# 1-Schematic_Macro_Pad.net
KiCad netlist of a schematic drawn in EasyEDA
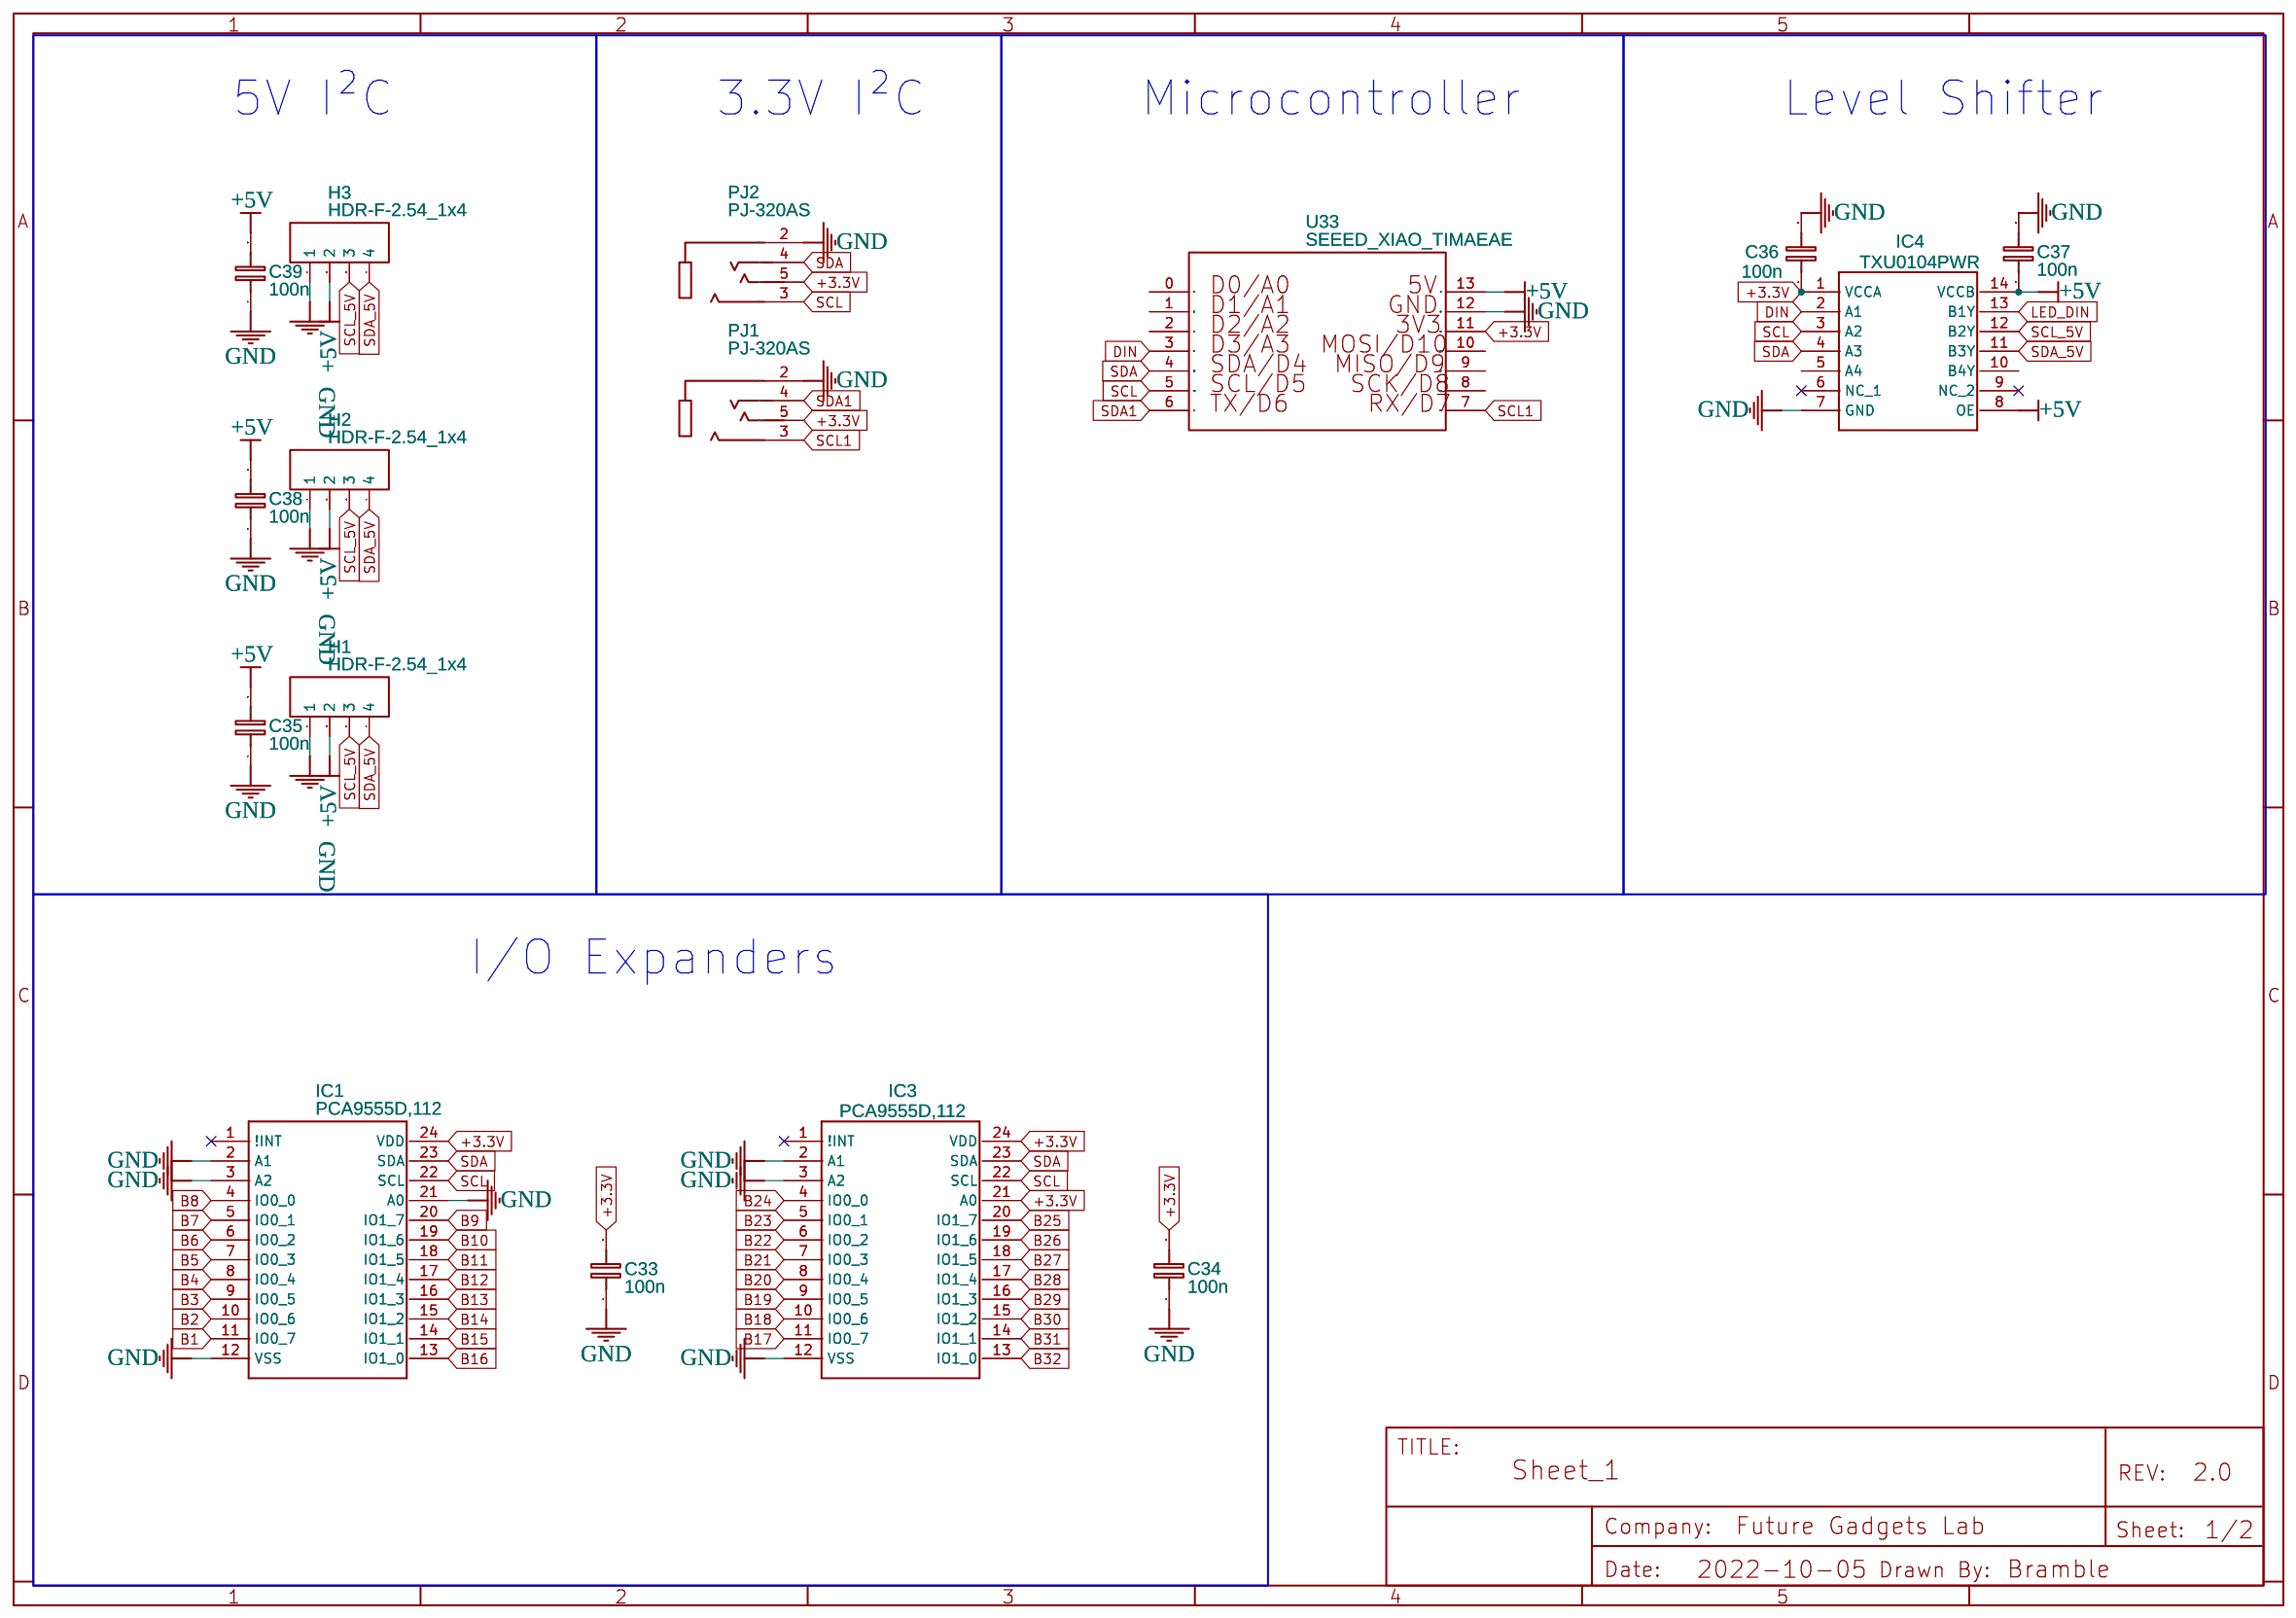
[diagram p0: Sheet_1]
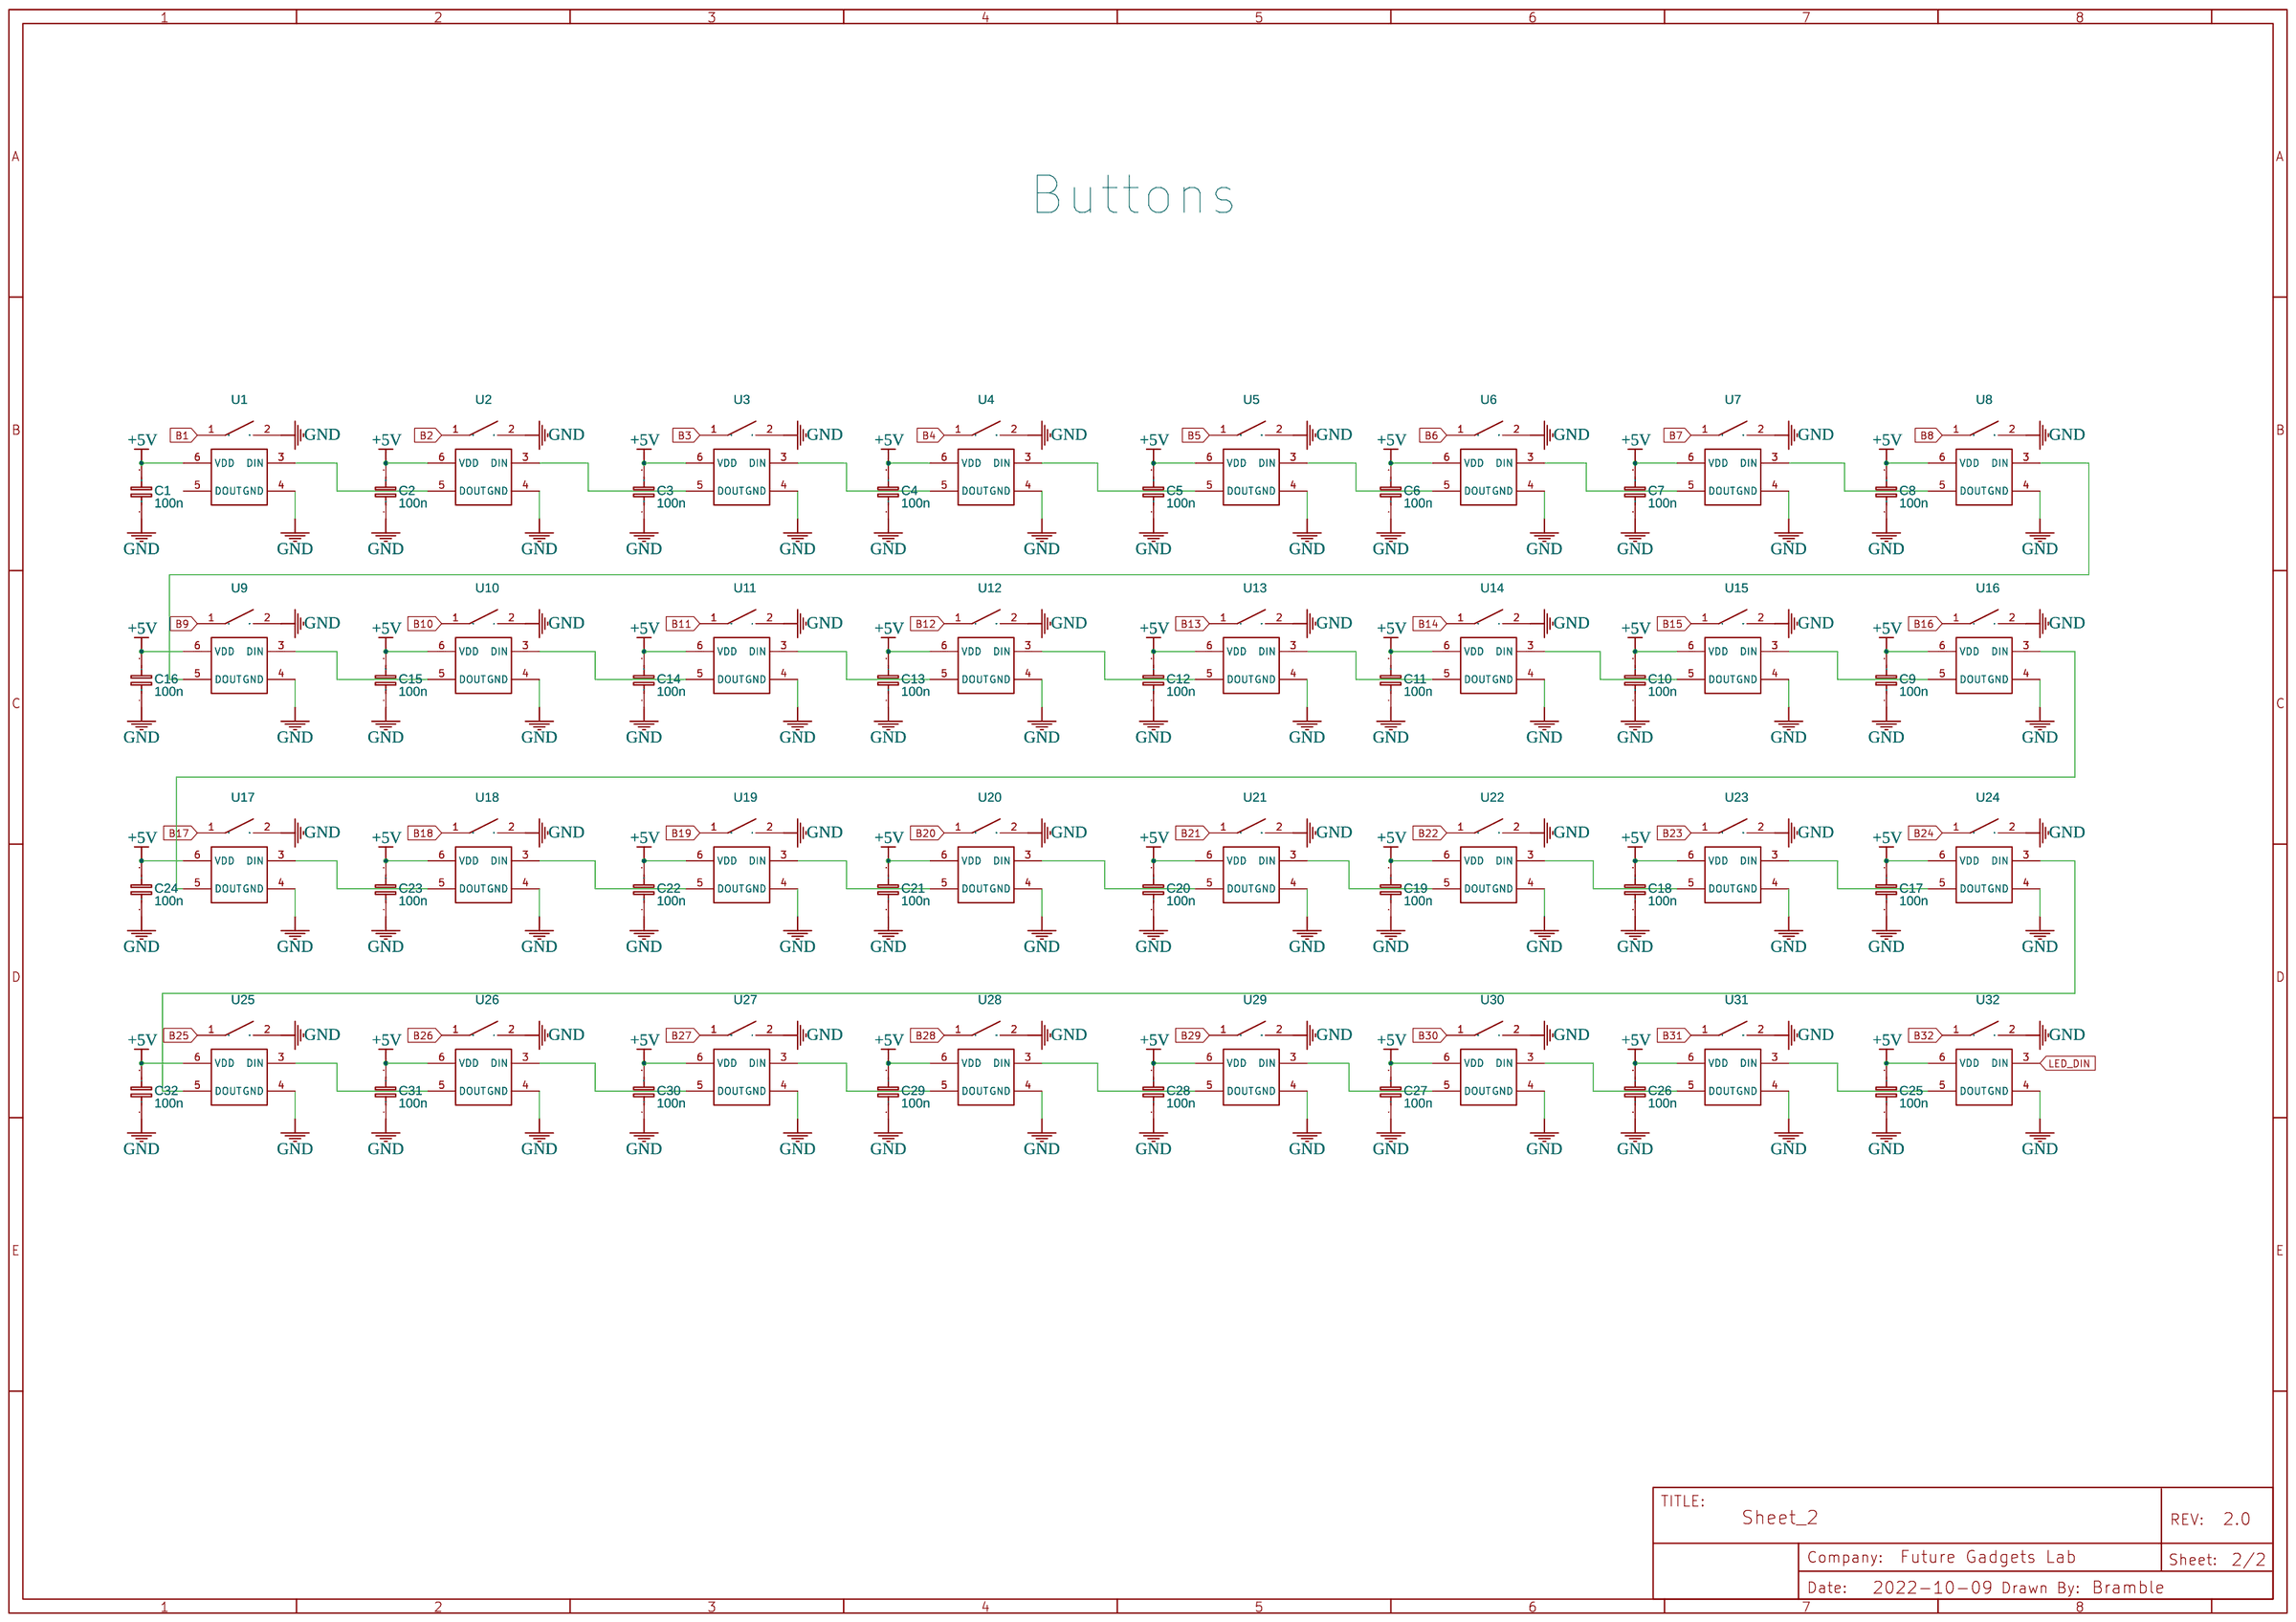
[diagram p1: Sheet_2]

(export (version "E")
  (design (tool "Eeschema 10.0.6"))
  (components
    (comp (ref "C33") (value "100n") (libsource (lib "") (part "C_0603_EU")))
    (comp (ref "C34") (value "100n") (libsource (lib "") (part "C_0603_EU_1")))
    (comp (ref "C35") (value "100n") (libsource (lib "") (part "C_0603_EU_1")))
    (comp (ref "C36") (value "100n") (libsource (lib "") (part "C_0603_EU_2")))
    (comp (ref "C37") (value "100n") (libsource (lib "") (part "C_0603_EU_2")))
    (comp (ref "C38") (value "100n") (libsource (lib "") (part "C_0603_EU_2")))
    (comp (ref "C39") (value "100n") (libsource (lib "") (part "C_0603_EU_2")))
    (comp (ref "H1")
      (value "HDR-F-2.54_1x4")
      (fields (field (name "BOM_Supplier Part") "C225501"))
      (libsource (lib "") (part "HDR-F-2.54_1x4"))
    )
    (comp (ref "H2")
      (value "HDR-F-2.54_1x4")
      (fields (field (name "BOM_Supplier Part") "C225501"))
      (libsource (lib "") (part "HDR-F-2.54_1x4"))
    )
    (comp (ref "H3")
      (value "HDR-F-2.54_1x4")
      (fields (field (name "BOM_Supplier Part") "C225501"))
      (libsource (lib "") (part "HDR-F-2.54_1x4"))
    )
    (comp (ref "IC1") (value "PCA9555D,112") (libsource (lib "") (part "PCA9555D,112")))
    (comp (ref "IC3") (value "PCA9555D,112") (libsource (lib "") (part "PCA9555D,112")))
    (comp (ref "IC4") (value "TXU0104PWR") (libsource (lib "") (part "TXU0104PWR")))
    (comp (ref "PJ1")
      (value "PJ-320AS")
      (fields (field (name "BOM_Supplier Part") "C2939182"))
      (libsource (lib "") (part "PJ-320AS"))
    )
    (comp (ref "PJ2")
      (value "PJ-320AS")
      (fields (field (name "BOM_Supplier Part") "C2939182"))
      (libsource (lib "") (part "PJ-320AS"))
    )
    (comp (ref "U33")
      (value "SEEED_XIAO_TIMAEAE")
      (fields (field (name "BOM_Manufacturer Part") "102010428"))
      (libsource (lib "") (part "SEEED_XIAO_TIMAEAE"))
    )
    (comp (ref "C1") (value "100n") (libsource (lib "") (part "C_0603_EU")))
    (comp (ref "C2") (value "100n") (libsource (lib "") (part "C_0603_EU_1")))
    (comp (ref "C3") (value "100n") (libsource (lib "") (part "C_0603_EU_1")))
    (comp (ref "C4") (value "100n") (libsource (lib "") (part "C_0603_EU")))
    (comp (ref "C5") (value "100n") (libsource (lib "") (part "C_0603_EU")))
    (comp (ref "C6") (value "100n") (libsource (lib "") (part "C_0603_EU")))
    (comp (ref "C7") (value "100n") (libsource (lib "") (part "C_0603_EU")))
    (comp (ref "C8") (value "100n") (libsource (lib "") (part "C_0603_EU")))
    (comp (ref "C9") (value "100n") (libsource (lib "") (part "C_0603_EU")))
    (comp (ref "C10") (value "100n") (libsource (lib "") (part "C_0603_EU")))
    (comp (ref "C11") (value "100n") (libsource (lib "") (part "C_0603_EU")))
    (comp (ref "C12") (value "100n") (libsource (lib "") (part "C_0603_EU")))
    (comp (ref "C13") (value "100n") (libsource (lib "") (part "C_0603_EU")))
    (comp (ref "C14") (value "100n") (libsource (lib "") (part "C_0603_EU_1")))
    (comp (ref "C15") (value "100n") (libsource (lib "") (part "C_0603_EU_1")))
    (comp (ref "C16") (value "100n") (libsource (lib "") (part "C_0603_EU")))
    (comp (ref "C17") (value "100n") (libsource (lib "") (part "C_0603_EU")))
    (comp (ref "C18") (value "100n") (libsource (lib "") (part "C_0603_EU")))
    (comp (ref "C19") (value "100n") (libsource (lib "") (part "C_0603_EU")))
    (comp (ref "C20") (value "100n") (libsource (lib "") (part "C_0603_EU")))
    (comp (ref "C21") (value "100n") (libsource (lib "") (part "C_0603_EU")))
    (comp (ref "C22") (value "100n") (libsource (lib "") (part "C_0603_EU_1")))
    (comp (ref "C23") (value "100n") (libsource (lib "") (part "C_0603_EU_1")))
    (comp (ref "C24") (value "100n") (libsource (lib "") (part "C_0603_EU")))
    (comp (ref "C25") (value "100n") (libsource (lib "") (part "C_0603_EU_3")))
    (comp (ref "C26") (value "100n") (libsource (lib "") (part "C_0603_EU_3")))
    (comp (ref "C27") (value "100n") (libsource (lib "") (part "C_0603_EU_3")))
    (comp (ref "C28") (value "100n") (libsource (lib "") (part "C_0603_EU_3")))
    (comp (ref "C29") (value "100n") (libsource (lib "") (part "C_0603_EU_3")))
    (comp (ref "C30") (value "100n") (libsource (lib "") (part "C_0603_EU_2")))
    (comp (ref "C31") (value "100n") (libsource (lib "") (part "C_0603_EU_2")))
    (comp (ref "C32") (value "100n") (libsource (lib "") (part "C_0603_EU_3")))
    (comp (ref "U1") (value "Hotswap MX/Choc 1*1") (libsource (lib "") (part "Hotswap MX/Choc 1*1")))
    (comp (ref "U2") (value "Hotswap MX/Choc 1*1") (libsource (lib "") (part "Hotswap MX/Choc 1*1")))
    (comp (ref "U3") (value "Hotswap MX/Choc 1*1") (libsource (lib "") (part "Hotswap MX/Choc 1*1")))
    (comp (ref "U4") (value "Hotswap MX/Choc 1*1") (libsource (lib "") (part "Hotswap MX/Choc 1*1")))
    (comp (ref "U5") (value "Hotswap MX/Choc 1*1") (libsource (lib "") (part "Hotswap MX/Choc 1*1")))
    (comp (ref "U6") (value "Hotswap MX/Choc 1*1") (libsource (lib "") (part "Hotswap MX/Choc 1*1")))
    (comp (ref "U7") (value "Hotswap MX/Choc 1*1") (libsource (lib "") (part "Hotswap MX/Choc 1*1")))
    (comp (ref "U8") (value "Hotswap MX/Choc 1*1") (libsource (lib "") (part "Hotswap MX/Choc 1*1")))
    (comp (ref "U9") (value "Hotswap MX/Choc 1*1") (libsource (lib "") (part "Hotswap MX/Choc 1*1")))
    (comp (ref "U10") (value "Hotswap MX/Choc 1*1") (libsource (lib "") (part "Hotswap MX/Choc 1*1")))
    (comp (ref "U11") (value "Hotswap MX/Choc 1*1") (libsource (lib "") (part "Hotswap MX/Choc 1*1")))
    (comp (ref "U12") (value "Hotswap MX/Choc 1*1") (libsource (lib "") (part "Hotswap MX/Choc 1*1")))
    (comp (ref "U13") (value "Hotswap MX/Choc 1*1") (libsource (lib "") (part "Hotswap MX/Choc 1*1")))
    (comp (ref "U14") (value "Hotswap MX/Choc 1*1") (libsource (lib "") (part "Hotswap MX/Choc 1*1")))
    (comp (ref "U15") (value "Hotswap MX/Choc 1*1") (libsource (lib "") (part "Hotswap MX/Choc 1*1")))
    (comp (ref "U16") (value "Hotswap MX/Choc 1*1") (libsource (lib "") (part "Hotswap MX/Choc 1*1")))
    (comp (ref "U17") (value "Hotswap MX/Choc 1*1") (libsource (lib "") (part "Hotswap MX/Choc 1*1")))
    (comp (ref "U18") (value "Hotswap MX/Choc 1*1") (libsource (lib "") (part "Hotswap MX/Choc 1*1")))
    (comp (ref "U19") (value "Hotswap MX/Choc 1*1") (libsource (lib "") (part "Hotswap MX/Choc 1*1")))
    (comp (ref "U20") (value "Hotswap MX/Choc 1*1") (libsource (lib "") (part "Hotswap MX/Choc 1*1")))
    (comp (ref "U21") (value "Hotswap MX/Choc 1*1") (libsource (lib "") (part "Hotswap MX/Choc 1*1")))
    (comp (ref "U22") (value "Hotswap MX/Choc 1*1") (libsource (lib "") (part "Hotswap MX/Choc 1*1")))
    (comp (ref "U23") (value "Hotswap MX/Choc 1*1") (libsource (lib "") (part "Hotswap MX/Choc 1*1")))
    (comp (ref "U24") (value "Hotswap MX/Choc 1*1") (libsource (lib "") (part "Hotswap MX/Choc 1*1")))
    (comp (ref "U25") (value "Hotswap MX/Choc 1*1") (libsource (lib "") (part "Hotswap MX/Choc 1*1")))
    (comp (ref "U26") (value "Hotswap MX/Choc 1*1") (libsource (lib "") (part "Hotswap MX/Choc 1*1")))
    (comp (ref "U27") (value "Hotswap MX/Choc 1*1") (libsource (lib "") (part "Hotswap MX/Choc 1*1")))
    (comp (ref "U28") (value "Hotswap MX/Choc 1*1") (libsource (lib "") (part "Hotswap MX/Choc 1*1")))
    (comp (ref "U29") (value "Hotswap MX/Choc 1*1") (libsource (lib "") (part "Hotswap MX/Choc 1*1")))
    (comp (ref "U30") (value "Hotswap MX/Choc 1*1") (libsource (lib "") (part "Hotswap MX/Choc 1*1")))
    (comp (ref "U31") (value "Hotswap MX/Choc 1*1") (libsource (lib "") (part "Hotswap MX/Choc 1*1")))
    (comp (ref "U32") (value "Hotswap MX/Choc 1*1") (libsource (lib "") (part "Hotswap MX/Choc 1*1")))
  )
  (nets
    (net (code "1") (name "+3.3V") (class "Default")
      (node (ref "C33") (pin "2") (pinfunction "2_2") (pintype "unspecified"))
      (node (ref "C34") (pin "2") (pinfunction "2_2") (pintype "unspecified"))
      (node (ref "C36") (pin "1") (pinfunction "1_1") (pintype "unspecified"))
      (node (ref "IC1") (pin "24") (pinfunction "VDD_24") (pintype "bidirectional"))
      (node (ref "IC3") (pin "21") (pinfunction "A0_21") (pintype "bidirectional"))
      (node (ref "IC3") (pin "24") (pinfunction "VDD_24") (pintype "bidirectional"))
      (node (ref "IC4") (pin "1") (pinfunction "VCCA_1") (pintype "bidirectional"))
      (node (ref "PJ1") (pin "5") (pinfunction "5_5") (pintype "unspecified"))
      (node (ref "PJ2") (pin "5") (pinfunction "5_5") (pintype "unspecified"))
      (node (ref "U33") (pin "11") (pinfunction "3V3_11") (pintype "unspecified"))
    )
    (net (code "2") (name "+5V") (class "Default")
      (node (ref "C1") (pin "2") (pinfunction "2_2") (pintype "unspecified"))
      (node (ref "C10") (pin "2") (pinfunction "2_2") (pintype "unspecified"))
      (node (ref "C11") (pin "2") (pinfunction "2_2") (pintype "unspecified"))
      (node (ref "C12") (pin "2") (pinfunction "2_2") (pintype "unspecified"))
      (node (ref "C13") (pin "2") (pinfunction "2_2") (pintype "unspecified"))
      (node (ref "C14") (pin "2") (pinfunction "2_2") (pintype "unspecified"))
      (node (ref "C15") (pin "2") (pinfunction "2_2") (pintype "unspecified"))
      (node (ref "C16") (pin "2") (pinfunction "2_2") (pintype "unspecified"))
      (node (ref "C17") (pin "2") (pinfunction "2_2") (pintype "unspecified"))
      (node (ref "C18") (pin "2") (pinfunction "2_2") (pintype "unspecified"))
      (node (ref "C19") (pin "2") (pinfunction "2_2") (pintype "unspecified"))
      (node (ref "C2") (pin "2") (pinfunction "2_2") (pintype "unspecified"))
      (node (ref "C20") (pin "2") (pinfunction "2_2") (pintype "unspecified"))
      (node (ref "C21") (pin "2") (pinfunction "2_2") (pintype "unspecified"))
      (node (ref "C22") (pin "2") (pinfunction "2_2") (pintype "unspecified"))
      (node (ref "C23") (pin "2") (pinfunction "2_2") (pintype "unspecified"))
      (node (ref "C24") (pin "2") (pinfunction "2_2") (pintype "unspecified"))
      (node (ref "C25") (pin "2") (pinfunction "2_2") (pintype "unspecified"))
      (node (ref "C26") (pin "2") (pinfunction "2_2") (pintype "unspecified"))
      (node (ref "C27") (pin "2") (pinfunction "2_2") (pintype "unspecified"))
      (node (ref "C28") (pin "2") (pinfunction "2_2") (pintype "unspecified"))
      (node (ref "C29") (pin "2") (pinfunction "2_2") (pintype "unspecified"))
      (node (ref "C3") (pin "2") (pinfunction "2_2") (pintype "unspecified"))
      (node (ref "C30") (pin "2") (pinfunction "2_2") (pintype "unspecified"))
      (node (ref "C31") (pin "2") (pinfunction "2_2") (pintype "unspecified"))
      (node (ref "C32") (pin "2") (pinfunction "2_2") (pintype "unspecified"))
      (node (ref "C35") (pin "2") (pinfunction "2_2") (pintype "unspecified"))
      (node (ref "C37") (pin "1") (pinfunction "1_1") (pintype "unspecified"))
      (node (ref "C38") (pin "2") (pinfunction "2_2") (pintype "unspecified"))
      (node (ref "C39") (pin "2") (pinfunction "2_2") (pintype "unspecified"))
      (node (ref "C4") (pin "2") (pinfunction "2_2") (pintype "unspecified"))
      (node (ref "C5") (pin "2") (pinfunction "2_2") (pintype "unspecified"))
      (node (ref "C6") (pin "2") (pinfunction "2_2") (pintype "unspecified"))
      (node (ref "C7") (pin "2") (pinfunction "2_2") (pintype "unspecified"))
      (node (ref "C8") (pin "2") (pinfunction "2_2") (pintype "unspecified"))
      (node (ref "C9") (pin "2") (pinfunction "2_2") (pintype "unspecified"))
      (node (ref "H1") (pin "2") (pinfunction "2_2") (pintype "unspecified"))
      (node (ref "H2") (pin "2") (pinfunction "2_2") (pintype "unspecified"))
      (node (ref "H3") (pin "2") (pinfunction "2_2") (pintype "unspecified"))
      (node (ref "IC4") (pin "14") (pinfunction "VCCB_14") (pintype "bidirectional"))
      (node (ref "IC4") (pin "8") (pinfunction "OE_8") (pintype "bidirectional"))
      (node (ref "U1") (pin "6") (pinfunction "VDD_6") (pintype "unspecified"))
      (node (ref "U10") (pin "6") (pinfunction "VDD_6") (pintype "unspecified"))
      (node (ref "U11") (pin "6") (pinfunction "VDD_6") (pintype "unspecified"))
      (node (ref "U12") (pin "6") (pinfunction "VDD_6") (pintype "unspecified"))
      (node (ref "U13") (pin "6") (pinfunction "VDD_6") (pintype "unspecified"))
      (node (ref "U14") (pin "6") (pinfunction "VDD_6") (pintype "unspecified"))
      (node (ref "U15") (pin "6") (pinfunction "VDD_6") (pintype "unspecified"))
      (node (ref "U16") (pin "6") (pinfunction "VDD_6") (pintype "unspecified"))
      (node (ref "U17") (pin "6") (pinfunction "VDD_6") (pintype "unspecified"))
      (node (ref "U18") (pin "6") (pinfunction "VDD_6") (pintype "unspecified"))
      (node (ref "U19") (pin "6") (pinfunction "VDD_6") (pintype "unspecified"))
      (node (ref "U2") (pin "6") (pinfunction "VDD_6") (pintype "unspecified"))
      (node (ref "U20") (pin "6") (pinfunction "VDD_6") (pintype "unspecified"))
      (node (ref "U21") (pin "6") (pinfunction "VDD_6") (pintype "unspecified"))
      (node (ref "U22") (pin "6") (pinfunction "VDD_6") (pintype "unspecified"))
      (node (ref "U23") (pin "6") (pinfunction "VDD_6") (pintype "unspecified"))
      (node (ref "U24") (pin "6") (pinfunction "VDD_6") (pintype "unspecified"))
      (node (ref "U25") (pin "6") (pinfunction "VDD_6") (pintype "unspecified"))
      (node (ref "U26") (pin "6") (pinfunction "VDD_6") (pintype "unspecified"))
      (node (ref "U27") (pin "6") (pinfunction "VDD_6") (pintype "unspecified"))
      (node (ref "U28") (pin "6") (pinfunction "VDD_6") (pintype "unspecified"))
      (node (ref "U29") (pin "6") (pinfunction "VDD_6") (pintype "unspecified"))
      (node (ref "U3") (pin "6") (pinfunction "VDD_6") (pintype "unspecified"))
      (node (ref "U30") (pin "6") (pinfunction "VDD_6") (pintype "unspecified"))
      (node (ref "U31") (pin "6") (pinfunction "VDD_6") (pintype "unspecified"))
      (node (ref "U32") (pin "6") (pinfunction "VDD_6") (pintype "unspecified"))
      (node (ref "U33") (pin "13") (pinfunction "SV_13") (pintype "unspecified"))
      (node (ref "U4") (pin "6") (pinfunction "VDD_6") (pintype "unspecified"))
      (node (ref "U5") (pin "6") (pinfunction "VDD_6") (pintype "unspecified"))
      (node (ref "U6") (pin "6") (pinfunction "VDD_6") (pintype "unspecified"))
      (node (ref "U7") (pin "6") (pinfunction "VDD_6") (pintype "unspecified"))
      (node (ref "U8") (pin "6") (pinfunction "VDD_6") (pintype "unspecified"))
      (node (ref "U9") (pin "6") (pinfunction "VDD_6") (pintype "unspecified"))
    )
    (net (code "3") (name "B1") (class "Default")
      (node (ref "IC1") (pin "11") (pinfunction "IO0_7_11") (pintype "bidirectional"))
      (node (ref "U1") (pin "1") (pinfunction "SW1_1") (pintype "unspecified"))
    )
    (net (code "4") (name "B2") (class "Default")
      (node (ref "IC1") (pin "10") (pinfunction "IO0_6_10") (pintype "bidirectional"))
      (node (ref "U2") (pin "1") (pinfunction "SW1_1") (pintype "unspecified"))
    )
    (net (code "5") (name "B3") (class "Default")
      (node (ref "IC1") (pin "9") (pinfunction "IO0_5_9") (pintype "bidirectional"))
      (node (ref "U3") (pin "1") (pinfunction "SW1_1") (pintype "unspecified"))
    )
    (net (code "6") (name "B4") (class "Default")
      (node (ref "IC1") (pin "8") (pinfunction "IO0_4_8") (pintype "bidirectional"))
      (node (ref "U4") (pin "1") (pinfunction "SW1_1") (pintype "unspecified"))
    )
    (net (code "7") (name "B5") (class "Default")
      (node (ref "IC1") (pin "7") (pinfunction "IO0_3_7") (pintype "bidirectional"))
      (node (ref "U5") (pin "1") (pinfunction "SW1_1") (pintype "unspecified"))
    )
    (net (code "8") (name "B6") (class "Default")
      (node (ref "IC1") (pin "6") (pinfunction "IO0_2_6") (pintype "bidirectional"))
      (node (ref "U6") (pin "1") (pinfunction "SW1_1") (pintype "unspecified"))
    )
    (net (code "9") (name "B7") (class "Default")
      (node (ref "IC1") (pin "5") (pinfunction "IO0_1_5") (pintype "bidirectional"))
      (node (ref "U7") (pin "1") (pinfunction "SW1_1") (pintype "unspecified"))
    )
    (net (code "10") (name "B8") (class "Default")
      (node (ref "IC1") (pin "4") (pinfunction "IO0_0_4") (pintype "bidirectional"))
      (node (ref "U8") (pin "1") (pinfunction "SW1_1") (pintype "unspecified"))
    )
    (net (code "11") (name "B9") (class "Default")
      (node (ref "IC1") (pin "20") (pinfunction "IO1_7_20") (pintype "bidirectional"))
      (node (ref "U9") (pin "1") (pinfunction "SW1_1") (pintype "unspecified"))
    )
    (net (code "12") (name "B10") (class "Default")
      (node (ref "IC1") (pin "19") (pinfunction "IO1_6_19") (pintype "bidirectional"))
      (node (ref "U10") (pin "1") (pinfunction "SW1_1") (pintype "unspecified"))
    )
    (net (code "13") (name "B11") (class "Default")
      (node (ref "IC1") (pin "18") (pinfunction "IO1_5_18") (pintype "bidirectional"))
      (node (ref "U11") (pin "1") (pinfunction "SW1_1") (pintype "unspecified"))
    )
    (net (code "14") (name "B12") (class "Default")
      (node (ref "IC1") (pin "17") (pinfunction "IO1_4_17") (pintype "bidirectional"))
      (node (ref "U12") (pin "1") (pinfunction "SW1_1") (pintype "unspecified"))
    )
    (net (code "15") (name "B13") (class "Default")
      (node (ref "IC1") (pin "16") (pinfunction "IO1_3_16") (pintype "bidirectional"))
      (node (ref "U13") (pin "1") (pinfunction "SW1_1") (pintype "unspecified"))
    )
    (net (code "16") (name "B14") (class "Default")
      (node (ref "IC1") (pin "15") (pinfunction "IO1_2_15") (pintype "bidirectional"))
      (node (ref "U14") (pin "1") (pinfunction "SW1_1") (pintype "unspecified"))
    )
    (net (code "17") (name "B15") (class "Default")
      (node (ref "IC1") (pin "14") (pinfunction "IO1_1_14") (pintype "bidirectional"))
      (node (ref "U15") (pin "1") (pinfunction "SW1_1") (pintype "unspecified"))
    )
    (net (code "18") (name "B16") (class "Default")
      (node (ref "IC1") (pin "13") (pinfunction "IO1_0_13") (pintype "bidirectional"))
      (node (ref "U16") (pin "1") (pinfunction "SW1_1") (pintype "unspecified"))
    )
    (net (code "19") (name "B17") (class "Default")
      (node (ref "IC3") (pin "11") (pinfunction "IO0_7_11") (pintype "bidirectional"))
      (node (ref "U17") (pin "1") (pinfunction "SW1_1") (pintype "unspecified"))
    )
    (net (code "20") (name "B18") (class "Default")
      (node (ref "IC3") (pin "10") (pinfunction "IO0_6_10") (pintype "bidirectional"))
      (node (ref "U18") (pin "1") (pinfunction "SW1_1") (pintype "unspecified"))
    )
    (net (code "21") (name "B19") (class "Default")
      (node (ref "IC3") (pin "9") (pinfunction "IO0_5_9") (pintype "bidirectional"))
      (node (ref "U19") (pin "1") (pinfunction "SW1_1") (pintype "unspecified"))
    )
    (net (code "22") (name "B20") (class "Default")
      (node (ref "IC3") (pin "8") (pinfunction "IO0_4_8") (pintype "bidirectional"))
      (node (ref "U20") (pin "1") (pinfunction "SW1_1") (pintype "unspecified"))
    )
    (net (code "23") (name "B21") (class "Default")
      (node (ref "IC3") (pin "7") (pinfunction "IO0_3_7") (pintype "bidirectional"))
      (node (ref "U21") (pin "1") (pinfunction "SW1_1") (pintype "unspecified"))
    )
    (net (code "24") (name "B22") (class "Default")
      (node (ref "IC3") (pin "6") (pinfunction "IO0_2_6") (pintype "bidirectional"))
      (node (ref "U22") (pin "1") (pinfunction "SW1_1") (pintype "unspecified"))
    )
    (net (code "25") (name "B23") (class "Default")
      (node (ref "IC3") (pin "5") (pinfunction "IO0_1_5") (pintype "bidirectional"))
      (node (ref "U23") (pin "1") (pinfunction "SW1_1") (pintype "unspecified"))
    )
    (net (code "26") (name "B24") (class "Default")
      (node (ref "IC3") (pin "4") (pinfunction "IO0_0_4") (pintype "bidirectional"))
      (node (ref "U24") (pin "1") (pinfunction "SW1_1") (pintype "unspecified"))
    )
    (net (code "27") (name "B25") (class "Default")
      (node (ref "IC3") (pin "20") (pinfunction "IO1_7_20") (pintype "bidirectional"))
      (node (ref "U25") (pin "1") (pinfunction "SW1_1") (pintype "unspecified"))
    )
    (net (code "28") (name "B26") (class "Default")
      (node (ref "IC3") (pin "19") (pinfunction "IO1_6_19") (pintype "bidirectional"))
      (node (ref "U26") (pin "1") (pinfunction "SW1_1") (pintype "unspecified"))
    )
    (net (code "29") (name "B27") (class "Default")
      (node (ref "IC3") (pin "18") (pinfunction "IO1_5_18") (pintype "bidirectional"))
      (node (ref "U27") (pin "1") (pinfunction "SW1_1") (pintype "unspecified"))
    )
    (net (code "30") (name "B28") (class "Default")
      (node (ref "IC3") (pin "17") (pinfunction "IO1_4_17") (pintype "bidirectional"))
      (node (ref "U28") (pin "1") (pinfunction "SW1_1") (pintype "unspecified"))
    )
    (net (code "31") (name "B29") (class "Default")
      (node (ref "IC3") (pin "16") (pinfunction "IO1_3_16") (pintype "bidirectional"))
      (node (ref "U29") (pin "1") (pinfunction "SW1_1") (pintype "unspecified"))
    )
    (net (code "32") (name "B30") (class "Default")
      (node (ref "IC3") (pin "15") (pinfunction "IO1_2_15") (pintype "bidirectional"))
      (node (ref "U30") (pin "1") (pinfunction "SW1_1") (pintype "unspecified"))
    )
    (net (code "33") (name "B31") (class "Default")
      (node (ref "IC3") (pin "14") (pinfunction "IO1_1_14") (pintype "bidirectional"))
      (node (ref "U31") (pin "1") (pinfunction "SW1_1") (pintype "unspecified"))
    )
    (net (code "34") (name "B32") (class "Default")
      (node (ref "IC3") (pin "13") (pinfunction "IO1_0_13") (pintype "bidirectional"))
      (node (ref "U32") (pin "1") (pinfunction "SW1_1") (pintype "unspecified"))
    )
    (net (code "35") (name "DIN") (class "Default")
      (node (ref "IC4") (pin "2") (pinfunction "A1_2") (pintype "bidirectional"))
      (node (ref "U33") (pin "3") (pinfunction "D3/A3_3") (pintype "unspecified"))
    )
    (net (code "36") (name "GND") (class "Default")
      (node (ref "C1") (pin "1") (pinfunction "1_1") (pintype "unspecified"))
      (node (ref "C10") (pin "1") (pinfunction "1_1") (pintype "unspecified"))
      (node (ref "C11") (pin "1") (pinfunction "1_1") (pintype "unspecified"))
      (node (ref "C12") (pin "1") (pinfunction "1_1") (pintype "unspecified"))
      (node (ref "C13") (pin "1") (pinfunction "1_1") (pintype "unspecified"))
      (node (ref "C14") (pin "1") (pinfunction "1_1") (pintype "unspecified"))
      (node (ref "C15") (pin "1") (pinfunction "1_1") (pintype "unspecified"))
      (node (ref "C16") (pin "1") (pinfunction "1_1") (pintype "unspecified"))
      (node (ref "C17") (pin "1") (pinfunction "1_1") (pintype "unspecified"))
      (node (ref "C18") (pin "1") (pinfunction "1_1") (pintype "unspecified"))
      (node (ref "C19") (pin "1") (pinfunction "1_1") (pintype "unspecified"))
      (node (ref "C2") (pin "1") (pinfunction "1_1") (pintype "unspecified"))
      (node (ref "C20") (pin "1") (pinfunction "1_1") (pintype "unspecified"))
      (node (ref "C21") (pin "1") (pinfunction "1_1") (pintype "unspecified"))
      (node (ref "C22") (pin "1") (pinfunction "1_1") (pintype "unspecified"))
      (node (ref "C23") (pin "1") (pinfunction "1_1") (pintype "unspecified"))
      (node (ref "C24") (pin "1") (pinfunction "1_1") (pintype "unspecified"))
      (node (ref "C25") (pin "1") (pinfunction "1_1") (pintype "unspecified"))
      (node (ref "C26") (pin "1") (pinfunction "1_1") (pintype "unspecified"))
      (node (ref "C27") (pin "1") (pinfunction "1_1") (pintype "unspecified"))
      (node (ref "C28") (pin "1") (pinfunction "1_1") (pintype "unspecified"))
      (node (ref "C29") (pin "1") (pinfunction "1_1") (pintype "unspecified"))
      (node (ref "C3") (pin "1") (pinfunction "1_1") (pintype "unspecified"))
      (node (ref "C30") (pin "1") (pinfunction "1_1") (pintype "unspecified"))
      (node (ref "C31") (pin "1") (pinfunction "1_1") (pintype "unspecified"))
      (node (ref "C32") (pin "1") (pinfunction "1_1") (pintype "unspecified"))
      (node (ref "C33") (pin "1") (pinfunction "1_1") (pintype "unspecified"))
      (node (ref "C34") (pin "1") (pinfunction "1_1") (pintype "unspecified"))
      (node (ref "C35") (pin "1") (pinfunction "1_1") (pintype "unspecified"))
      (node (ref "C36") (pin "2") (pinfunction "2_2") (pintype "unspecified"))
      (node (ref "C37") (pin "2") (pinfunction "2_2") (pintype "unspecified"))
      (node (ref "C38") (pin "1") (pinfunction "1_1") (pintype "unspecified"))
      (node (ref "C39") (pin "1") (pinfunction "1_1") (pintype "unspecified"))
      (node (ref "C4") (pin "1") (pinfunction "1_1") (pintype "unspecified"))
      (node (ref "C5") (pin "1") (pinfunction "1_1") (pintype "unspecified"))
      (node (ref "C6") (pin "1") (pinfunction "1_1") (pintype "unspecified"))
      (node (ref "C7") (pin "1") (pinfunction "1_1") (pintype "unspecified"))
      (node (ref "C8") (pin "1") (pinfunction "1_1") (pintype "unspecified"))
      (node (ref "C9") (pin "1") (pinfunction "1_1") (pintype "unspecified"))
      (node (ref "H1") (pin "1") (pinfunction "1_1") (pintype "unspecified"))
      (node (ref "H2") (pin "1") (pinfunction "1_1") (pintype "unspecified"))
      (node (ref "H3") (pin "1") (pinfunction "1_1") (pintype "unspecified"))
      (node (ref "IC1") (pin "12") (pinfunction "VSS_12") (pintype "bidirectional"))
      (node (ref "IC1") (pin "2") (pinfunction "A1_2") (pintype "bidirectional"))
      (node (ref "IC1") (pin "21") (pinfunction "A0_21") (pintype "bidirectional"))
      (node (ref "IC1") (pin "3") (pinfunction "A2_3") (pintype "bidirectional"))
      (node (ref "IC3") (pin "12") (pinfunction "VSS_12") (pintype "bidirectional"))
      (node (ref "IC3") (pin "2") (pinfunction "A1_2") (pintype "bidirectional"))
      (node (ref "IC3") (pin "3") (pinfunction "A2_3") (pintype "bidirectional"))
      (node (ref "IC4") (pin "7") (pinfunction "GND_7") (pintype "bidirectional"))
      (node (ref "PJ1") (pin "2") (pinfunction "2_2") (pintype "unspecified"))
      (node (ref "PJ2") (pin "2") (pinfunction "2_2") (pintype "unspecified"))
      (node (ref "U1") (pin "2") (pinfunction "SW2_2") (pintype "unspecified"))
      (node (ref "U1") (pin "4") (pinfunction "GND_4") (pintype "unspecified"))
      (node (ref "U10") (pin "2") (pinfunction "SW2_2") (pintype "unspecified"))
      (node (ref "U10") (pin "4") (pinfunction "GND_4") (pintype "unspecified"))
      (node (ref "U11") (pin "2") (pinfunction "SW2_2") (pintype "unspecified"))
      (node (ref "U11") (pin "4") (pinfunction "GND_4") (pintype "unspecified"))
      (node (ref "U12") (pin "2") (pinfunction "SW2_2") (pintype "unspecified"))
      (node (ref "U12") (pin "4") (pinfunction "GND_4") (pintype "unspecified"))
      (node (ref "U13") (pin "2") (pinfunction "SW2_2") (pintype "unspecified"))
      (node (ref "U13") (pin "4") (pinfunction "GND_4") (pintype "unspecified"))
      (node (ref "U14") (pin "2") (pinfunction "SW2_2") (pintype "unspecified"))
      (node (ref "U14") (pin "4") (pinfunction "GND_4") (pintype "unspecified"))
      (node (ref "U15") (pin "2") (pinfunction "SW2_2") (pintype "unspecified"))
      (node (ref "U15") (pin "4") (pinfunction "GND_4") (pintype "unspecified"))
      (node (ref "U16") (pin "2") (pinfunction "SW2_2") (pintype "unspecified"))
      (node (ref "U16") (pin "4") (pinfunction "GND_4") (pintype "unspecified"))
      (node (ref "U17") (pin "2") (pinfunction "SW2_2") (pintype "unspecified"))
      (node (ref "U17") (pin "4") (pinfunction "GND_4") (pintype "unspecified"))
      (node (ref "U18") (pin "2") (pinfunction "SW2_2") (pintype "unspecified"))
      (node (ref "U18") (pin "4") (pinfunction "GND_4") (pintype "unspecified"))
      (node (ref "U19") (pin "2") (pinfunction "SW2_2") (pintype "unspecified"))
      (node (ref "U19") (pin "4") (pinfunction "GND_4") (pintype "unspecified"))
      (node (ref "U2") (pin "2") (pinfunction "SW2_2") (pintype "unspecified"))
      (node (ref "U2") (pin "4") (pinfunction "GND_4") (pintype "unspecified"))
      (node (ref "U20") (pin "2") (pinfunction "SW2_2") (pintype "unspecified"))
      (node (ref "U20") (pin "4") (pinfunction "GND_4") (pintype "unspecified"))
      (node (ref "U21") (pin "2") (pinfunction "SW2_2") (pintype "unspecified"))
      (node (ref "U21") (pin "4") (pinfunction "GND_4") (pintype "unspecified"))
      (node (ref "U22") (pin "2") (pinfunction "SW2_2") (pintype "unspecified"))
      (node (ref "U22") (pin "4") (pinfunction "GND_4") (pintype "unspecified"))
      (node (ref "U23") (pin "2") (pinfunction "SW2_2") (pintype "unspecified"))
      (node (ref "U23") (pin "4") (pinfunction "GND_4") (pintype "unspecified"))
      (node (ref "U24") (pin "2") (pinfunction "SW2_2") (pintype "unspecified"))
      (node (ref "U24") (pin "4") (pinfunction "GND_4") (pintype "unspecified"))
      (node (ref "U25") (pin "2") (pinfunction "SW2_2") (pintype "unspecified"))
      (node (ref "U25") (pin "4") (pinfunction "GND_4") (pintype "unspecified"))
      (node (ref "U26") (pin "2") (pinfunction "SW2_2") (pintype "unspecified"))
      (node (ref "U26") (pin "4") (pinfunction "GND_4") (pintype "unspecified"))
      (node (ref "U27") (pin "2") (pinfunction "SW2_2") (pintype "unspecified"))
      (node (ref "U27") (pin "4") (pinfunction "GND_4") (pintype "unspecified"))
      (node (ref "U28") (pin "2") (pinfunction "SW2_2") (pintype "unspecified"))
      (node (ref "U28") (pin "4") (pinfunction "GND_4") (pintype "unspecified"))
      (node (ref "U29") (pin "2") (pinfunction "SW2_2") (pintype "unspecified"))
      (node (ref "U29") (pin "4") (pinfunction "GND_4") (pintype "unspecified"))
      (node (ref "U3") (pin "2") (pinfunction "SW2_2") (pintype "unspecified"))
      (node (ref "U3") (pin "4") (pinfunction "GND_4") (pintype "unspecified"))
      (node (ref "U30") (pin "2") (pinfunction "SW2_2") (pintype "unspecified"))
      (node (ref "U30") (pin "4") (pinfunction "GND_4") (pintype "unspecified"))
      (node (ref "U31") (pin "2") (pinfunction "SW2_2") (pintype "unspecified"))
      (node (ref "U31") (pin "4") (pinfunction "GND_4") (pintype "unspecified"))
      (node (ref "U32") (pin "2") (pinfunction "SW2_2") (pintype "unspecified"))
      (node (ref "U32") (pin "4") (pinfunction "GND_4") (pintype "unspecified"))
      (node (ref "U33") (pin "12") (pinfunction "GND_12") (pintype "unspecified"))
      (node (ref "U4") (pin "2") (pinfunction "SW2_2") (pintype "unspecified"))
      (node (ref "U4") (pin "4") (pinfunction "GND_4") (pintype "unspecified"))
      (node (ref "U5") (pin "2") (pinfunction "SW2_2") (pintype "unspecified"))
      (node (ref "U5") (pin "4") (pinfunction "GND_4") (pintype "unspecified"))
      (node (ref "U6") (pin "2") (pinfunction "SW2_2") (pintype "unspecified"))
      (node (ref "U6") (pin "4") (pinfunction "GND_4") (pintype "unspecified"))
      (node (ref "U7") (pin "2") (pinfunction "SW2_2") (pintype "unspecified"))
      (node (ref "U7") (pin "4") (pinfunction "GND_4") (pintype "unspecified"))
      (node (ref "U8") (pin "2") (pinfunction "SW2_2") (pintype "unspecified"))
      (node (ref "U8") (pin "4") (pinfunction "GND_4") (pintype "unspecified"))
      (node (ref "U9") (pin "2") (pinfunction "SW2_2") (pintype "unspecified"))
      (node (ref "U9") (pin "4") (pinfunction "GND_4") (pintype "unspecified"))
    )
    (net (code "37") (name "LED_DIN") (class "Default")
      (node (ref "IC4") (pin "13") (pinfunction "B1Y_13") (pintype "bidirectional"))
      (node (ref "U32") (pin "3") (pinfunction "DIN_3") (pintype "unspecified"))
    )
    (net (code "38") (name "Net-(U1-DIN)") (class "Default")
      (node (ref "U1") (pin "3") (pinfunction "DIN_3") (pintype "unspecified"))
      (node (ref "U2") (pin "5") (pinfunction "DOUT_5") (pintype "unspecified"))
    )
    (net (code "39") (name "Net-(U2-DIN)") (class "Default")
      (node (ref "U2") (pin "3") (pinfunction "DIN_3") (pintype "unspecified"))
      (node (ref "U3") (pin "5") (pinfunction "DOUT_5") (pintype "unspecified"))
    )
    (net (code "40") (name "Net-(U3-DIN)") (class "Default")
      (node (ref "U3") (pin "3") (pinfunction "DIN_3") (pintype "unspecified"))
      (node (ref "U4") (pin "5") (pinfunction "DOUT_5") (pintype "unspecified"))
    )
    (net (code "41") (name "Net-(U4-DIN)") (class "Default")
      (node (ref "U4") (pin "3") (pinfunction "DIN_3") (pintype "unspecified"))
      (node (ref "U5") (pin "5") (pinfunction "DOUT_5") (pintype "unspecified"))
    )
    (net (code "42") (name "Net-(U5-DIN)") (class "Default")
      (node (ref "U5") (pin "3") (pinfunction "DIN_3") (pintype "unspecified"))
      (node (ref "U6") (pin "5") (pinfunction "DOUT_5") (pintype "unspecified"))
    )
    (net (code "43") (name "Net-(U6-DIN)") (class "Default")
      (node (ref "U6") (pin "3") (pinfunction "DIN_3") (pintype "unspecified"))
      (node (ref "U7") (pin "5") (pinfunction "DOUT_5") (pintype "unspecified"))
    )
    (net (code "44") (name "Net-(U7-DIN)") (class "Default")
      (node (ref "U7") (pin "3") (pinfunction "DIN_3") (pintype "unspecified"))
      (node (ref "U8") (pin "5") (pinfunction "DOUT_5") (pintype "unspecified"))
    )
    (net (code "45") (name "Net-(U8-DIN)") (class "Default")
      (node (ref "U8") (pin "3") (pinfunction "DIN_3") (pintype "unspecified"))
      (node (ref "U9") (pin "5") (pinfunction "DOUT_5") (pintype "unspecified"))
    )
    (net (code "46") (name "Net-(U10-DIN)") (class "Default")
      (node (ref "U10") (pin "3") (pinfunction "DIN_3") (pintype "unspecified"))
      (node (ref "U11") (pin "5") (pinfunction "DOUT_5") (pintype "unspecified"))
    )
    (net (code "47") (name "Net-(U10-DOUT)") (class "Default")
      (node (ref "U10") (pin "5") (pinfunction "DOUT_5") (pintype "unspecified"))
      (node (ref "U9") (pin "3") (pinfunction "DIN_3") (pintype "unspecified"))
    )
    (net (code "48") (name "Net-(U11-DIN)") (class "Default")
      (node (ref "U11") (pin "3") (pinfunction "DIN_3") (pintype "unspecified"))
      (node (ref "U12") (pin "5") (pinfunction "DOUT_5") (pintype "unspecified"))
    )
    (net (code "49") (name "Net-(U12-DIN)") (class "Default")
      (node (ref "U12") (pin "3") (pinfunction "DIN_3") (pintype "unspecified"))
      (node (ref "U13") (pin "5") (pinfunction "DOUT_5") (pintype "unspecified"))
    )
    (net (code "50") (name "Net-(U13-DIN)") (class "Default")
      (node (ref "U13") (pin "3") (pinfunction "DIN_3") (pintype "unspecified"))
      (node (ref "U14") (pin "5") (pinfunction "DOUT_5") (pintype "unspecified"))
    )
    (net (code "51") (name "Net-(U14-DIN)") (class "Default")
      (node (ref "U14") (pin "3") (pinfunction "DIN_3") (pintype "unspecified"))
      (node (ref "U15") (pin "5") (pinfunction "DOUT_5") (pintype "unspecified"))
    )
    (net (code "52") (name "Net-(U15-DIN)") (class "Default")
      (node (ref "U15") (pin "3") (pinfunction "DIN_3") (pintype "unspecified"))
      (node (ref "U16") (pin "5") (pinfunction "DOUT_5") (pintype "unspecified"))
    )
    (net (code "53") (name "Net-(U16-DIN)") (class "Default")
      (node (ref "U16") (pin "3") (pinfunction "DIN_3") (pintype "unspecified"))
      (node (ref "U17") (pin "5") (pinfunction "DOUT_5") (pintype "unspecified"))
    )
    (net (code "54") (name "Net-(U17-DIN)") (class "Default")
      (node (ref "U17") (pin "3") (pinfunction "DIN_3") (pintype "unspecified"))
      (node (ref "U18") (pin "5") (pinfunction "DOUT_5") (pintype "unspecified"))
    )
    (net (code "55") (name "Net-(U18-DIN)") (class "Default")
      (node (ref "U18") (pin "3") (pinfunction "DIN_3") (pintype "unspecified"))
      (node (ref "U19") (pin "5") (pinfunction "DOUT_5") (pintype "unspecified"))
    )
    (net (code "56") (name "Net-(U19-DIN)") (class "Default")
      (node (ref "U19") (pin "3") (pinfunction "DIN_3") (pintype "unspecified"))
      (node (ref "U20") (pin "5") (pinfunction "DOUT_5") (pintype "unspecified"))
    )
    (net (code "57") (name "Net-(U20-DIN)") (class "Default")
      (node (ref "U20") (pin "3") (pinfunction "DIN_3") (pintype "unspecified"))
      (node (ref "U21") (pin "5") (pinfunction "DOUT_5") (pintype "unspecified"))
    )
    (net (code "58") (name "Net-(U21-DIN)") (class "Default")
      (node (ref "U21") (pin "3") (pinfunction "DIN_3") (pintype "unspecified"))
      (node (ref "U22") (pin "5") (pinfunction "DOUT_5") (pintype "unspecified"))
    )
    (net (code "59") (name "Net-(U22-DIN)") (class "Default")
      (node (ref "U22") (pin "3") (pinfunction "DIN_3") (pintype "unspecified"))
      (node (ref "U23") (pin "5") (pinfunction "DOUT_5") (pintype "unspecified"))
    )
    (net (code "60") (name "Net-(U23-DIN)") (class "Default")
      (node (ref "U23") (pin "3") (pinfunction "DIN_3") (pintype "unspecified"))
      (node (ref "U24") (pin "5") (pinfunction "DOUT_5") (pintype "unspecified"))
    )
    (net (code "61") (name "Net-(U24-DIN)") (class "Default")
      (node (ref "U24") (pin "3") (pinfunction "DIN_3") (pintype "unspecified"))
      (node (ref "U25") (pin "5") (pinfunction "DOUT_5") (pintype "unspecified"))
    )
    (net (code "62") (name "Net-(U25-DIN)") (class "Default")
      (node (ref "U25") (pin "3") (pinfunction "DIN_3") (pintype "unspecified"))
      (node (ref "U26") (pin "5") (pinfunction "DOUT_5") (pintype "unspecified"))
    )
    (net (code "63") (name "Net-(U26-DIN)") (class "Default")
      (node (ref "U26") (pin "3") (pinfunction "DIN_3") (pintype "unspecified"))
      (node (ref "U27") (pin "5") (pinfunction "DOUT_5") (pintype "unspecified"))
    )
    (net (code "64") (name "Net-(U27-DIN)") (class "Default")
      (node (ref "U27") (pin "3") (pinfunction "DIN_3") (pintype "unspecified"))
      (node (ref "U28") (pin "5") (pinfunction "DOUT_5") (pintype "unspecified"))
    )
    (net (code "65") (name "Net-(U28-DIN)") (class "Default")
      (node (ref "U28") (pin "3") (pinfunction "DIN_3") (pintype "unspecified"))
      (node (ref "U29") (pin "5") (pinfunction "DOUT_5") (pintype "unspecified"))
    )
    (net (code "66") (name "Net-(U29-DIN)") (class "Default")
      (node (ref "U29") (pin "3") (pinfunction "DIN_3") (pintype "unspecified"))
      (node (ref "U30") (pin "5") (pinfunction "DOUT_5") (pintype "unspecified"))
    )
    (net (code "67") (name "Net-(U30-DIN)") (class "Default")
      (node (ref "U30") (pin "3") (pinfunction "DIN_3") (pintype "unspecified"))
      (node (ref "U31") (pin "5") (pinfunction "DOUT_5") (pintype "unspecified"))
    )
    (net (code "68") (name "Net-(U31-DIN)") (class "Default")
      (node (ref "U31") (pin "3") (pinfunction "DIN_3") (pintype "unspecified"))
      (node (ref "U32") (pin "5") (pinfunction "DOUT_5") (pintype "unspecified"))
    )
    (net (code "69") (name "SCL") (class "Default")
      (node (ref "IC1") (pin "22") (pinfunction "SCL_22") (pintype "bidirectional"))
      (node (ref "IC3") (pin "22") (pinfunction "SCL_22") (pintype "bidirectional"))
      (node (ref "IC4") (pin "3") (pinfunction "A2_3") (pintype "bidirectional"))
      (node (ref "PJ2") (pin "3") (pinfunction "3_3") (pintype "unspecified"))
      (node (ref "U33") (pin "5") (pinfunction "SCL/D5_5") (pintype "unspecified"))
    )
    (net (code "70") (name "SCL1") (class "Default")
      (node (ref "PJ1") (pin "3") (pinfunction "3_3") (pintype "unspecified"))
      (node (ref "U33") (pin "7") (pinfunction "RX/D7_7") (pintype "unspecified"))
    )
    (net (code "71") (name "SCL_5V") (class "Default")
      (node (ref "H1") (pin "3") (pinfunction "3_3") (pintype "unspecified"))
      (node (ref "H2") (pin "3") (pinfunction "3_3") (pintype "unspecified"))
      (node (ref "H3") (pin "3") (pinfunction "3_3") (pintype "unspecified"))
      (node (ref "IC4") (pin "12") (pinfunction "B2Y_12") (pintype "bidirectional"))
    )
    (net (code "72") (name "SDA") (class "Default")
      (node (ref "IC1") (pin "23") (pinfunction "SDA_23") (pintype "bidirectional"))
      (node (ref "IC3") (pin "23") (pinfunction "SDA_23") (pintype "bidirectional"))
      (node (ref "IC4") (pin "4") (pinfunction "A3_4") (pintype "bidirectional"))
      (node (ref "PJ2") (pin "4") (pinfunction "4_4") (pintype "unspecified"))
      (node (ref "U33") (pin "4") (pinfunction "SDA/D4_4") (pintype "unspecified"))
    )
    (net (code "73") (name "SDA1") (class "Default")
      (node (ref "PJ1") (pin "4") (pinfunction "4_4") (pintype "unspecified"))
      (node (ref "U33") (pin "6") (pinfunction "TX/D6_6") (pintype "unspecified"))
    )
    (net (code "74") (name "SDA_5V") (class "Default")
      (node (ref "H1") (pin "4") (pinfunction "4_4") (pintype "unspecified"))
      (node (ref "H2") (pin "4") (pinfunction "4_4") (pintype "unspecified"))
      (node (ref "H3") (pin "4") (pinfunction "4_4") (pintype "unspecified"))
      (node (ref "IC4") (pin "11") (pinfunction "B3Y_11") (pintype "bidirectional"))
    )
    (net (code "75") (name "unconnected-(IC1-!INT-Pad1)") (class "Default")
      (node (ref "IC1") (pin "1") (pinfunction "!INT_1") (pintype "bidirectional+no_connect"))
    )
    (net (code "76") (name "unconnected-(IC3-!INT-Pad1)") (class "Default")
      (node (ref "IC3") (pin "1") (pinfunction "!INT_1") (pintype "bidirectional+no_connect"))
    )
    (net (code "77") (name "unconnected-(IC4-A4-Pad5)") (class "Default")
      (node (ref "IC4") (pin "5") (pinfunction "A4_5") (pintype "bidirectional"))
    )
    (net (code "78") (name "unconnected-(IC4-B4Y-Pad10)") (class "Default")
      (node (ref "IC4") (pin "10") (pinfunction "B4Y_10") (pintype "bidirectional"))
    )
    (net (code "79") (name "unconnected-(IC4-NC_1-Pad6)") (class "Default")
      (node (ref "IC4") (pin "6") (pinfunction "NC_1_6") (pintype "bidirectional+no_connect"))
    )
    (net (code "80") (name "unconnected-(IC4-NC_2-Pad9)") (class "Default")
      (node (ref "IC4") (pin "9") (pinfunction "NC_2_9") (pintype "bidirectional+no_connect"))
    )
    (net (code "81") (name "unconnected-(U1-DOUT-Pad5)") (class "Default")
      (node (ref "U1") (pin "5") (pinfunction "DOUT_5") (pintype "unspecified"))
    )
    (net (code "82") (name "unconnected-(U33-D0{slash}A0-Pad0)") (class "Default")
      (node (ref "U33") (pin "0") (pinfunction "D0/A0_0") (pintype "unspecified"))
    )
    (net (code "83") (name "unconnected-(U33-D1{slash}A1-Pad1)") (class "Default")
      (node (ref "U33") (pin "1") (pinfunction "D1/A1_1") (pintype "unspecified"))
    )
    (net (code "84") (name "unconnected-(U33-D2{slash}A2-Pad2)") (class "Default")
      (node (ref "U33") (pin "2") (pinfunction "D2/A2_2") (pintype "unspecified"))
    )
    (net (code "85") (name "unconnected-(U33-MISO{slash}D9-Pad9)") (class "Default")
      (node (ref "U33") (pin "9") (pinfunction "MISO/D9_9") (pintype "unspecified"))
    )
    (net (code "86") (name "unconnected-(U33-MOSI{slash}D10-Pad10)") (class "Default")
      (node (ref "U33") (pin "10") (pinfunction "MOSI/D10_10") (pintype "unspecified"))
    )
    (net (code "87") (name "unconnected-(U33-SCK{slash}D8-Pad8)") (class "Default")
      (node (ref "U33") (pin "8") (pinfunction "SCK/D8_8") (pintype "unspecified"))
    )
  )
)
